# USB.net
KiCad netlist of a schematic drawn in Altium Designer
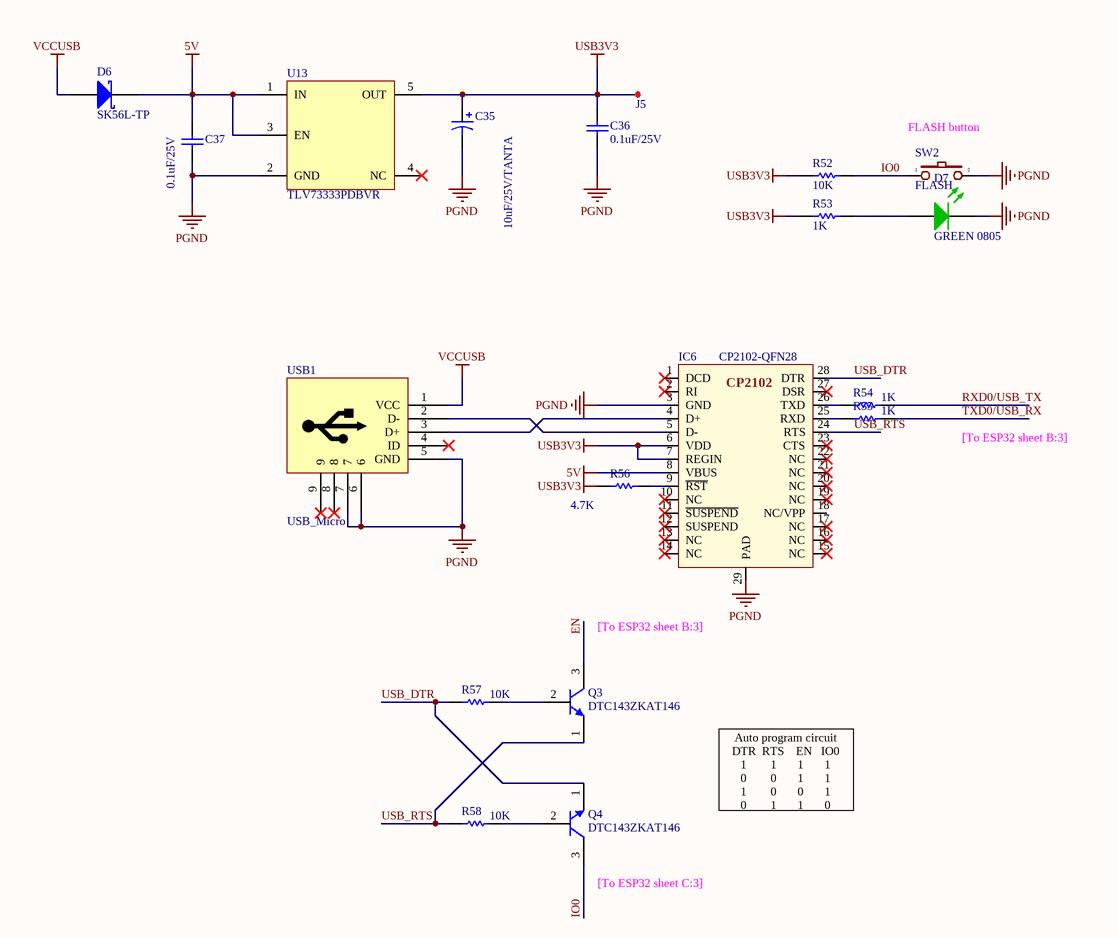
[diagram p0: USB.SchDoc]

(export (version "E")
  (design (tool "Eeschema 10.0.6"))
  (components
    (comp (ref "C35")
      (value "10uF/25V/TANTA")
      (footprint "CAP TANT CASE B SMD")
      (description "10µF Molded Tantalum Capacitors 25V 1411 (3528 Metric) 3 Ohm")
      (fields (field (name "MANUFACTURER") "KEMET"))
      (libsource (lib "GSHT_181013") (part "TAJB106M025RNJ"))
    )
    (comp (ref "C36")
      (value "0.1uF/25V")
      (footprint "CAP_CERA_C2012(CC0805INCH)")
      (description "0.1µF ±10% 25V Ceramic Capacitor X7R 0805 (2012 Metric)")
      (fields (field (name "MANUFACTURER") "KEMET"))
      (libsource (lib "GSHT_181013") (part "0.1uF/50V/C0603/10%"))
    )
    (comp (ref "C37")
      (value "0.1uF/25V")
      (footprint "CAP_CERA_C2012(CC0805INCH)")
      (description "0.1µF ±10% 25V Ceramic Capacitor X7R 0805 (2012 Metric)")
      (libsource (lib "GSHT_181013") (part "0.1uF/50V/C0603/10%"))
    )
    (comp (ref "D6")
      (value "SK56L-TP")
      (footprint "30# SK56L-TPMSCT-ND")
      (description "DIODE SCHOTTKY 60V 5A DO214AB")
      (libsource (lib "GSHT_181013") (part "30# SK56L-TP"))
    )
    (comp (ref "D7")
      (value "GREEN 0805")
      (footprint "Led 0805G")
      (description "Green 571nm LED Indication - Discrete 2V 0805 (2012 Metric)")
      (libsource (lib "GSHT_181013") (part "LED GREEN 0603"))
    )
    (comp (ref "IC6")
      (value "CP2102-QFN28")
      (footprint "CP2102-QFN28")
      (description "USB Bridge, USB to UART USB 2.0 UART Interface 28-QFN (5x5)")
      (libsource (lib "lpson") (part "CP2102"))
    )
    (comp (ref "J5")
      (value "TEST POINT")
      (footprint "TEST POINT 1mm")
      (description "TPoint")
      (libsource (lib "GSHT_181013") (part "PAD 1mm"))
    )
    (comp (ref "Q3")
      (value "DTC143ZKAT146")
      (footprint "6# DTC143ZKAT146-E")
      (description "Pre-Biased Bipolar Transistor (BJT) NPN - Pre-Biased 50V 100mA 250MHz 200mW Surface Mount SMT3")
      (libsource (lib "GSHT_181013") (part "6#DTC143ZKAT146"))
    )
    (comp (ref "Q4")
      (value "DTC143ZKAT146")
      (footprint "6# DTC143ZKAT146-E")
      (description "Pre-Biased Bipolar Transistor (BJT) NPN - Pre-Biased 50V 100mA 250MHz 200mW Surface Mount SMT3")
      (libsource (lib "GSHT_181013") (part "6#DTC143ZKAT146"))
    )
    (comp (ref "R52")
      (value "10K")
      (footprint "Res 0805 SMD")
      (description "10 kOhms ±1% 0.125W, 1/8W Chip Resistor 0805 (2012 Metric) Thick Film")
      (libsource (lib "GSHT_181013") (part "200K/R0603/1%"))
    )
    (comp (ref "R53")
      (value "1K")
      (footprint "Res 0805 SMD")
      (description "1 kOhms ±1% 0.125W, 1/8W Chip Resistor 0805 (2012 Metric) Automotive AEC-Q200 Thick Film")
      (libsource (lib "GSHT_181013") (part "200K/R0603/1%"))
    )
    (comp (ref "R54")
      (value "1K")
      (footprint "Res 0805 SMD")
      (description "1 kOhms ±1% 0.125W, 1/8W Chip Resistor 0805 (2012 Metric) Automotive AEC-Q200 Thick Film")
      (libsource (lib "GSHT_181013") (part "34.8K/R0805/1%"))
    )
    (comp (ref "R55")
      (value "1K")
      (footprint "Res 0805 SMD")
      (description "1 kOhms ±1% 0.125W, 1/8W Chip Resistor 0805 (2012 Metric) Automotive AEC-Q200 Thick Film")
      (libsource (lib "GSHT_181013") (part "34.8K/R0805/1%"))
    )
    (comp (ref "R56")
      (value "4.7K")
      (footprint "Res 0805 SMD")
      (description "4.7 kOhms ±1% 0.125W, 1/8W Chip Resistor 0805 (2012 Metric) Thick Film")
      (libsource (lib "GSHT_181013") (part "34.8K/R0805/1%"))
    )
    (comp (ref "R57")
      (value "10K")
      (footprint "Res 0805 SMD")
      (description "10 kOhms ±1% 0.125W, 1/8W Chip Resistor 0805 (2012 Metric) Thick Film")
      (libsource (lib "GSHT_181013") (part "34.8K/R0805/1%"))
    )
    (comp (ref "R58")
      (value "10K")
      (footprint "Res 0805 SMD")
      (description "10 kOhms ±1% 0.125W, 1/8W Chip Resistor 0805 (2012 Metric) Thick Film")
      (libsource (lib "GSHT_181013") (part "34.8K/R0805/1%"))
    )
    (comp (ref "SW2")
      (value "FLASH")
      (footprint "Button 3x4mm")
      (description "SWITCH TACTILE SPST-NO 0.05A 12V")
      (libsource (lib "lpson") (part "SW2"))
    )
    (comp (ref "U13")
      (value "TLV73333PDBVR")
      (footprint "20# TLV73333PDBVR - SOT23-65")
      (description "Linear Voltage Regulator IC Positive Fixed 1 Output 3.3V 300mA SOT-23-5")
      (libsource (lib "GSHT_181013") (part "20#TLV73333PDBVR"))
    )
    (comp (ref "USB1")
      (value "USB_Micro")
      (footprint "USB_MICRO_B - Digikey")
      (description "USB - micro B USB 2.0 Receptacle Connector 5 Position Surface Mount, Right Angle; Through Hole")
      (libsource (lib "lpson") (part "USB_MINI"))
    )
  )
  (nets
    (net (code "1") (name "/EN") (class "Default")
      (node (ref "Q3") (pin "3") (pinfunction "C_3") (pintype "passive"))
    )
    (net (code "2") (name "/IO0") (class "Default")
      (node (ref "Q4") (pin "3") (pinfunction "C_3") (pintype "passive"))
      (node (ref "R52") (pin "2") (pinfunction "2_2") (pintype "passive"))
      (node (ref "SW2") (pin "1") (pinfunction "1_1") (pintype "passive"))
    )
    (net (code "3") (name "/RXD0{slash}USB_TX") (class "Default")
      (node (ref "R54") (pin "1") (pinfunction "1_1") (pintype "passive"))
    )
    (net (code "4") (name "/TXD0{slash}USB_RX") (class "Default")
      (node (ref "R55") (pin "1") (pinfunction "1_1") (pintype "passive"))
    )
    (net (code "5") (name "/USB_DTR") (class "Default")
      (node (ref "IC6") (pin "28") (pinfunction "DTR_28") (pintype "passive"))
      (node (ref "Q4") (pin "1") (pinfunction "E_1") (pintype "passive"))
      (node (ref "R57") (pin "2") (pinfunction "2_2") (pintype "passive"))
    )
    (net (code "6") (name "/USB_RTS") (class "Default")
      (node (ref "IC6") (pin "24") (pinfunction "RTS_24") (pintype "passive"))
      (node (ref "Q3") (pin "1") (pinfunction "E_1") (pintype "passive"))
      (node (ref "R58") (pin "2") (pinfunction "2_2") (pintype "passive"))
    )
    (net (code "7") (name "5V") (class "Default")
      (node (ref "C37") (pin "2") (pinfunction "2_2") (pintype "passive"))
      (node (ref "D6") (pin "2") (pinfunction "K_2") (pintype "passive"))
      (node (ref "IC6") (pin "8") (pinfunction "VBUS_8") (pintype "passive"))
      (node (ref "U13") (pin "1") (pinfunction "IN_1") (pintype "passive"))
      (node (ref "U13") (pin "3") (pinfunction "EN_3") (pintype "passive"))
    )
    (net (code "8") (name "Net-(D7-A)") (class "Default")
      (node (ref "D7") (pin "1") (pinfunction "A_1") (pintype "passive"))
      (node (ref "R53") (pin "2") (pinfunction "2_2") (pintype "passive"))
    )
    (net (code "9") (name "Net-(IC6-D+)") (class "Default")
      (node (ref "IC6") (pin "4") (pinfunction "D+_4") (pintype "passive"))
      (node (ref "USB1") (pin "3") (pinfunction "D+_3") (pintype "passive"))
    )
    (net (code "10") (name "Net-(IC6-D-)") (class "Default")
      (node (ref "IC6") (pin "5") (pinfunction "D-_5") (pintype "passive"))
      (node (ref "USB1") (pin "2") (pinfunction "D-_2") (pintype "passive"))
    )
    (net (code "11") (name "Net-(IC6-RXD)") (class "Default")
      (node (ref "IC6") (pin "25") (pinfunction "RXD_25") (pintype "passive"))
      (node (ref "R55") (pin "2") (pinfunction "2_2") (pintype "passive"))
    )
    (net (code "12") (name "Net-(IC6-TXD)") (class "Default")
      (node (ref "IC6") (pin "26") (pinfunction "TXD_26") (pintype "passive"))
      (node (ref "R54") (pin "2") (pinfunction "2_2") (pintype "passive"))
    )
    (net (code "13") (name "Net-(IC6-~{RST})") (class "Default")
      (node (ref "IC6") (pin "9") (pinfunction "~{RST}_9") (pintype "passive"))
      (node (ref "R56") (pin "2") (pinfunction "2_2") (pintype "passive"))
    )
    (net (code "14") (name "Net-(Q3-B)") (class "Default")
      (node (ref "Q3") (pin "2") (pinfunction "B_2") (pintype "passive"))
      (node (ref "R57") (pin "1") (pinfunction "1_1") (pintype "passive"))
    )
    (net (code "15") (name "Net-(Q4-B)") (class "Default")
      (node (ref "Q4") (pin "2") (pinfunction "B_2") (pintype "passive"))
      (node (ref "R58") (pin "1") (pinfunction "1_1") (pintype "passive"))
    )
    (net (code "16") (name "PGND") (class "Default")
      (node (ref "C35") (pin "2") (pinfunction "2_2") (pintype "passive"))
      (node (ref "C36") (pin "1") (pinfunction "1_1") (pintype "passive"))
      (node (ref "C37") (pin "1") (pinfunction "1_1") (pintype "passive"))
      (node (ref "D7") (pin "2") (pinfunction "K_2") (pintype "passive"))
      (node (ref "IC6") (pin "29") (pinfunction "PAD_29") (pintype "passive"))
      (node (ref "IC6") (pin "3") (pinfunction "GND_3") (pintype "passive"))
      (node (ref "SW2") (pin "2") (pinfunction "2_2") (pintype "passive"))
      (node (ref "U13") (pin "2") (pinfunction "GND_2") (pintype "passive"))
      (node (ref "USB1") (pin "5") (pinfunction "GND_5") (pintype "passive"))
      (node (ref "USB1") (pin "6") (pinfunction "6_6") (pintype "passive"))
      (node (ref "USB1") (pin "7") (pinfunction "7_7") (pintype "passive"))
    )
    (net (code "17") (name "USB3V3") (class "Default")
      (node (ref "C35") (pin "1") (pinfunction "1_1") (pintype "passive"))
      (node (ref "C36") (pin "2") (pinfunction "2_2") (pintype "passive"))
      (node (ref "IC6") (pin "6") (pinfunction "VDD_6") (pintype "passive"))
      (node (ref "IC6") (pin "7") (pinfunction "REGIN_7") (pintype "passive"))
      (node (ref "J5") (pin "1") (pinfunction "TP_1") (pintype "passive"))
      (node (ref "R52") (pin "1") (pinfunction "1_1") (pintype "passive"))
      (node (ref "R53") (pin "1") (pinfunction "1_1") (pintype "passive"))
      (node (ref "R56") (pin "1") (pinfunction "1_1") (pintype "passive"))
      (node (ref "U13") (pin "5") (pinfunction "OUT_5") (pintype "passive"))
    )
    (net (code "18") (name "VCCUSB") (class "Default")
      (node (ref "D6") (pin "1") (pinfunction "A_1") (pintype "passive"))
      (node (ref "USB1") (pin "1") (pinfunction "VCC_1") (pintype "passive"))
    )
    (net (code "19") (name "unconnected-(IC6-CTS-Pad23)") (class "Default")
      (node (ref "IC6") (pin "23") (pinfunction "CTS_23") (pintype "passive+no_connect"))
    )
    (net (code "20") (name "unconnected-(IC6-DCD-Pad1)") (class "Default")
      (node (ref "IC6") (pin "1") (pinfunction "DCD_1") (pintype "passive+no_connect"))
    )
    (net (code "21") (name "unconnected-(IC6-DSR-Pad27)") (class "Default")
      (node (ref "IC6") (pin "27") (pinfunction "DSR_27") (pintype "passive+no_connect"))
    )
    (net (code "22") (name "unconnected-(IC6-NC-Pad10)") (class "Default")
      (node (ref "IC6") (pin "10") (pinfunction "NC_10") (pintype "passive+no_connect"))
    )
    (net (code "23") (name "unconnected-(IC6-NC-Pad13)") (class "Default")
      (node (ref "IC6") (pin "13") (pinfunction "NC_13") (pintype "passive+no_connect"))
    )
    (net (code "24") (name "unconnected-(IC6-NC-Pad14)") (class "Default")
      (node (ref "IC6") (pin "14") (pinfunction "NC_14") (pintype "passive+no_connect"))
    )
    (net (code "25") (name "unconnected-(IC6-NC-Pad15)") (class "Default")
      (node (ref "IC6") (pin "15") (pinfunction "NC_15") (pintype "passive+no_connect"))
    )
    (net (code "26") (name "unconnected-(IC6-NC-Pad16)") (class "Default")
      (node (ref "IC6") (pin "16") (pinfunction "NC_16") (pintype "passive+no_connect"))
    )
    (net (code "27") (name "unconnected-(IC6-NC-Pad17)") (class "Default")
      (node (ref "IC6") (pin "17") (pinfunction "NC_17") (pintype "passive+no_connect"))
    )
    (net (code "28") (name "unconnected-(IC6-NC-Pad19)") (class "Default")
      (node (ref "IC6") (pin "19") (pinfunction "NC_19") (pintype "passive+no_connect"))
    )
    (net (code "29") (name "unconnected-(IC6-NC-Pad20)") (class "Default")
      (node (ref "IC6") (pin "20") (pinfunction "NC_20") (pintype "passive+no_connect"))
    )
    (net (code "30") (name "unconnected-(IC6-NC-Pad21)") (class "Default")
      (node (ref "IC6") (pin "21") (pinfunction "NC_21") (pintype "passive+no_connect"))
    )
    (net (code "31") (name "unconnected-(IC6-NC-Pad22)") (class "Default")
      (node (ref "IC6") (pin "22") (pinfunction "NC_22") (pintype "passive+no_connect"))
    )
    (net (code "32") (name "unconnected-(IC6-NC{slash}VPP-Pad18)") (class "Default")
      (node (ref "IC6") (pin "18") (pinfunction "NC/VPP_18") (pintype "passive"))
    )
    (net (code "33") (name "unconnected-(IC6-RI-Pad2)") (class "Default")
      (node (ref "IC6") (pin "2") (pinfunction "RI_2") (pintype "passive+no_connect"))
    )
    (net (code "34") (name "unconnected-(IC6-SUSPEND-Pad12)") (class "Default")
      (node (ref "IC6") (pin "12") (pinfunction "SUSPEND_12") (pintype "passive+no_connect"))
    )
    (net (code "35") (name "unconnected-(IC6-~{SUSPEND}-Pad11)") (class "Default")
      (node (ref "IC6") (pin "11") (pinfunction "~{SUSPEND}_11") (pintype "passive+no_connect"))
    )
    (net (code "36") (name "unconnected-(U13-NC-Pad4)") (class "Default")
      (node (ref "U13") (pin "4") (pinfunction "NC_4") (pintype "passive+no_connect"))
    )
    (net (code "37") (name "unconnected-(USB1-ID-Pad4)") (class "Default")
      (node (ref "USB1") (pin "4") (pinfunction "ID_4") (pintype "passive+no_connect"))
    )
    (net (code "38") (name "unconnected-(USB1-Pad8)") (class "Default")
      (node (ref "USB1") (pin "8") (pinfunction "8_8") (pintype "passive+no_connect"))
    )
    (net (code "39") (name "unconnected-(USB1-Pad9)") (class "Default")
      (node (ref "USB1") (pin "9") (pinfunction "9_9") (pintype "passive+no_connect"))
    )
  )
)
